# EPS_MPPT_Y_OR_MPB.net
KiCad netlist of a schematic drawn in Altium Designer
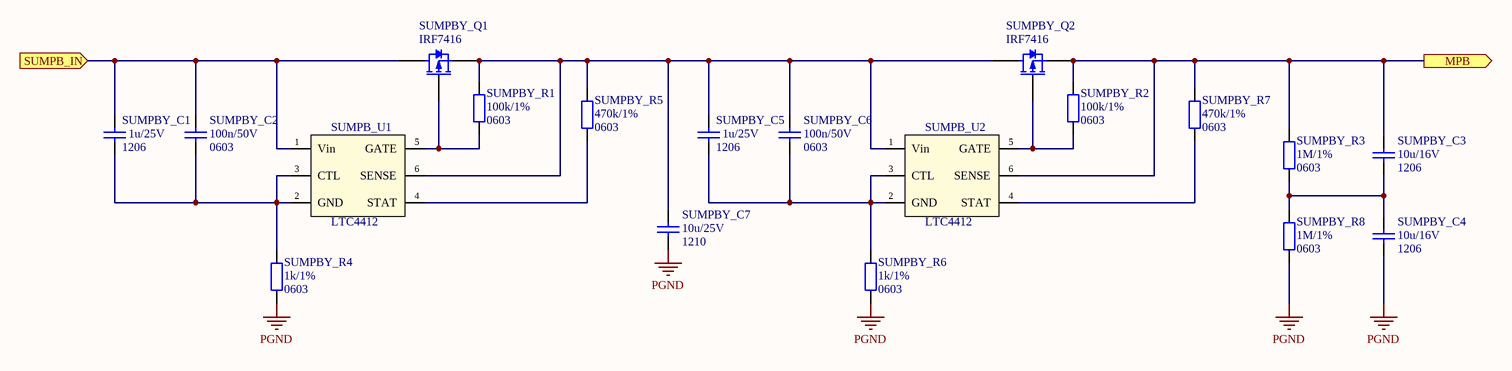
[diagram p0: EPS_MPPT_Y_OR_MPB.SchDoc]

(export (version "E")
  (design (tool "Eeschema 10.0.6"))
  (components
    (comp (ref "SUMPBY_C1")
      (value "1u/25V")
      (footprint "SMD_Capacitor_1206")
      (description "Ceramic Cap Kemet COTS 1u/25V X7R 1206")
      (fields
        (field (name "MANUFACTURERPARTNUMBER") "C1206T105K3RALTU")
        (field (name "MANUFACTURER") "Kemet")
        (field (name "PACKAGE") "1206")
      )
      (libsource (lib "capacitors") (part "Cer_C1206T105K3RALTU"))
    )
    (comp (ref "SUMPBY_C2")
      (value "100n/50V")
      (footprint "SMD_Capacitor_0603")
      (description "Ceramic Cap Murata Automotive 100n/50V X7R 0603")
      (fields
        (field (name "MANUFACTURER") "Murata")
        (field (name "MANUFACTURERPARTNUMBER") "GCJ188R71H104KA12D")
        (field (name "PACKAGE") "0603")
      )
      (libsource (lib "capacitors") (part "Cer_GCJ188R71H104KA12D"))
    )
    (comp (ref "SUMPBY_C3")
      (value "10u/16V")
      (footprint "SMD_Capacitor_1206")
      (description "Ceramic Cap Kemet COTS 10u/16V X7R 1206")
      (fields
        (field (name "MANUFACTURERPARTNUMBER") "C1206T106K4RACTU")
        (field (name "MANUFACTURER") "Kemet")
        (field (name "PACKGE") "1206")
      )
      (libsource (lib "capacitors") (part "Cer_C1206T106K4RACTU"))
    )
    (comp (ref "SUMPBY_C4")
      (value "10u/16V")
      (footprint "SMD_Capacitor_1206")
      (description "Ceramic Cap Kemet COTS 10u/16V X7R 1206")
      (fields
        (field (name "MANUFACTURERPARTNUMBER") "C1206T106K4RACTU")
        (field (name "MANUFACTURER") "Kemet")
        (field (name "PACKGE") "1206")
      )
      (libsource (lib "capacitors") (part "Cer_C1206T106K4RACTU"))
    )
    (comp (ref "SUMPBY_C5")
      (value "1u/25V")
      (footprint "SMD_Capacitor_1206")
      (description "Ceramic Cap Kemet COTS 1u/25V X7R 1206")
      (fields
        (field (name "MANUFACTURERPARTNUMBER") "C1206T105K3RALTU")
        (field (name "MANUFACTURER") "Kemet")
        (field (name "PACKAGE") "1206")
      )
      (libsource (lib "capacitors") (part "Cer_C1206T105K3RALTU"))
    )
    (comp (ref "SUMPBY_C6")
      (value "100n/50V")
      (footprint "SMD_Capacitor_0603")
      (description "Ceramic Cap Murata Automotive 100n/50V X7R 0603")
      (fields
        (field (name "MANUFACTURER") "Murata")
        (field (name "MANUFACTURERPARTNUMBER") "GCJ188R71H104KA12D")
        (field (name "PACKAGE") "0603")
      )
      (libsource (lib "capacitors") (part "Cer_GCJ188R71H104KA12D"))
    )
    (comp (ref "SUMPBY_C7")
      (value "10u/25V")
      (footprint "SMD_Capacitor_1210")
      (description "Ceramic Cap Murata Automotive 10u/25V X7R 1210")
      (fields
        (field (name "MANUFACTURER") "Murata")
        (field (name "MANUFACTURERPARTNUMBER") "GCJ32ER71E106KA12L")
        (field (name "PACKAGE") "1210")
      )
      (libsource (lib "capacitors") (part "Cer_GCJ32ER71E106KA12L"))
    )
    (comp (ref "SUMPBY_Q1")
      (value "IRF7416")
      (footprint "SOIC-8-N_SSSGDDDD")
      (description "10A/30V HEXFET Power P-MOSFET.")
      (fields (field (name "MANUFACTURER") "International Rectifier"))
      (libsource (lib "transistors") (part "IRF7416"))
    )
    (comp (ref "SUMPBY_Q2")
      (value "IRF7416")
      (footprint "SOIC-8-N_SSSGDDDD")
      (description "10A/30V HEXFET Power P-MOSFET.")
      (fields (field (name "MANUFACTURER") "International Rectifier"))
      (libsource (lib "transistors") (part "IRF7416"))
    )
    (comp (ref "SUMPBY_R1")
      (value "100k/1%")
      (footprint "SMD_Resistor_0603")
      (fields (field (name "PACKAGE") "0603"))
      (libsource (lib "resistors") (part "Res"))
    )
    (comp (ref "SUMPBY_R2")
      (value "100k/1%")
      (footprint "SMD_Resistor_0603")
      (fields (field (name "PACKAGE") "0603"))
      (libsource (lib "resistors") (part "Res"))
    )
    (comp (ref "SUMPBY_R3")
      (value "1M/1%")
      (footprint "SMD_Resistor_0603")
      (fields (field (name "PACKAGE") "0603"))
      (libsource (lib "resistors") (part "Res"))
    )
    (comp (ref "SUMPBY_R4")
      (value "1k/1%")
      (footprint "SMD_Resistor_0603")
      (fields (field (name "PACKAGE") "0603"))
      (libsource (lib "resistors") (part "Res"))
    )
    (comp (ref "SUMPBY_R5")
      (value "470k/1%")
      (footprint "SMD_Resistor_0603")
      (fields (field (name "PACKAGE") "0603"))
      (libsource (lib "resistors") (part "Res"))
    )
    (comp (ref "SUMPBY_R6")
      (value "1k/1%")
      (footprint "SMD_Resistor_0603")
      (fields (field (name "PACKAGE") "0603"))
      (libsource (lib "resistors") (part "Res"))
    )
    (comp (ref "SUMPBY_R7")
      (value "470k/1%")
      (footprint "SMD_Resistor_0603")
      (fields (field (name "PACKAGE") "0603"))
      (libsource (lib "resistors") (part "Res"))
    )
    (comp (ref "SUMPBY_R8")
      (value "1M/1%")
      (footprint "SMD_Resistor_0603")
      (fields (field (name "PACKAGE") "0603"))
      (libsource (lib "resistors") (part "Res"))
    )
    (comp (ref "SUMPB_U1")
      (value "LTC4412")
      (footprint "SOT23-6")
      (description "Ideal Diode, Low Loss PowerPath Controller.")
      (fields (field (name "MANUFACTURER") "Linear Technology"))
      (libsource (lib "microcircuits") (part "LTC4412"))
    )
    (comp (ref "SUMPB_U2")
      (value "LTC4412")
      (footprint "SOT23-6")
      (description "Ideal Diode, Low Loss PowerPath Controller.")
      (fields (field (name "MANUFACTURER") "Linear Technology"))
      (libsource (lib "microcircuits") (part "LTC4412"))
    )
  )
  (nets
    (net (code "1") (name "/MPB") (class "Default")
      (node (ref "SUMPBY_C3") (pin "1") (pinfunction "1_1") (pintype "passive"))
      (node (ref "SUMPBY_Q2") (pin "S") (pinfunction "S_S") (pintype "passive"))
      (node (ref "SUMPBY_R2") (pin "1") (pinfunction "1_1") (pintype "passive"))
      (node (ref "SUMPBY_R3") (pin "1") (pinfunction "1_1") (pintype "passive"))
      (node (ref "SUMPBY_R7") (pin "1") (pinfunction "1_1") (pintype "passive"))
      (node (ref "SUMPB_U2") (pin "6") (pinfunction "SENSE_6") (pintype "passive"))
    )
    (net (code "2") (name "/SUMPB_IN") (class "Default")
      (node (ref "SUMPBY_C1") (pin "1") (pinfunction "1_1") (pintype "passive"))
      (node (ref "SUMPBY_C2") (pin "1") (pinfunction "1_1") (pintype "passive"))
      (node (ref "SUMPBY_Q1") (pin "D") (pinfunction "D_D") (pintype "passive"))
      (node (ref "SUMPB_U1") (pin "1") (pinfunction "Vin_1") (pintype "passive"))
    )
    (net (code "3") (name "Net-(SUMPBY_C3-Pad2)") (class "Default")
      (node (ref "SUMPBY_C3") (pin "2") (pinfunction "2_2") (pintype "passive"))
      (node (ref "SUMPBY_C4") (pin "1") (pinfunction "1_1") (pintype "passive"))
      (node (ref "SUMPBY_R3") (pin "2") (pinfunction "2_2") (pintype "passive"))
      (node (ref "SUMPBY_R8") (pin "1") (pinfunction "1_1") (pintype "passive"))
    )
    (net (code "4") (name "Net-(SUMPB_U1-CTL)") (class "Default")
      (node (ref "SUMPBY_C1") (pin "2") (pinfunction "2_2") (pintype "passive"))
      (node (ref "SUMPBY_C2") (pin "2") (pinfunction "2_2") (pintype "passive"))
      (node (ref "SUMPBY_R4") (pin "1") (pinfunction "1_1") (pintype "passive"))
      (node (ref "SUMPB_U1") (pin "2") (pinfunction "GND_2") (pintype "passive"))
      (node (ref "SUMPB_U1") (pin "3") (pinfunction "CTL_3") (pintype "passive"))
    )
    (net (code "5") (name "Net-(SUMPB_U1-GATE)") (class "Default")
      (node (ref "SUMPBY_Q1") (pin "G") (pinfunction "G_G") (pintype "passive"))
      (node (ref "SUMPBY_R1") (pin "2") (pinfunction "2_2") (pintype "passive"))
      (node (ref "SUMPB_U1") (pin "5") (pinfunction "GATE_5") (pintype "passive"))
    )
    (net (code "6") (name "Net-(SUMPB_U1-SENSE)") (class "Default")
      (node (ref "SUMPBY_C5") (pin "1") (pinfunction "1_1") (pintype "passive"))
      (node (ref "SUMPBY_C6") (pin "1") (pinfunction "1_1") (pintype "passive"))
      (node (ref "SUMPBY_C7") (pin "1") (pinfunction "1_1") (pintype "passive"))
      (node (ref "SUMPBY_Q1") (pin "S") (pinfunction "S_S") (pintype "passive"))
      (node (ref "SUMPBY_Q2") (pin "D") (pinfunction "D_D") (pintype "passive"))
      (node (ref "SUMPBY_R1") (pin "1") (pinfunction "1_1") (pintype "passive"))
      (node (ref "SUMPBY_R5") (pin "1") (pinfunction "1_1") (pintype "passive"))
      (node (ref "SUMPB_U1") (pin "6") (pinfunction "SENSE_6") (pintype "passive"))
      (node (ref "SUMPB_U2") (pin "1") (pinfunction "Vin_1") (pintype "passive"))
    )
    (net (code "7") (name "Net-(SUMPB_U1-STAT)") (class "Default")
      (node (ref "SUMPBY_R5") (pin "2") (pinfunction "2_2") (pintype "passive"))
      (node (ref "SUMPB_U1") (pin "4") (pinfunction "STAT_4") (pintype "passive"))
    )
    (net (code "8") (name "Net-(SUMPB_U2-CTL)") (class "Default")
      (node (ref "SUMPBY_C5") (pin "2") (pinfunction "2_2") (pintype "passive"))
      (node (ref "SUMPBY_C6") (pin "2") (pinfunction "2_2") (pintype "passive"))
      (node (ref "SUMPBY_R6") (pin "1") (pinfunction "1_1") (pintype "passive"))
      (node (ref "SUMPB_U2") (pin "2") (pinfunction "GND_2") (pintype "passive"))
      (node (ref "SUMPB_U2") (pin "3") (pinfunction "CTL_3") (pintype "passive"))
    )
    (net (code "9") (name "Net-(SUMPB_U2-GATE)") (class "Default")
      (node (ref "SUMPBY_Q2") (pin "G") (pinfunction "G_G") (pintype "passive"))
      (node (ref "SUMPBY_R2") (pin "2") (pinfunction "2_2") (pintype "passive"))
      (node (ref "SUMPB_U2") (pin "5") (pinfunction "GATE_5") (pintype "passive"))
    )
    (net (code "10") (name "Net-(SUMPB_U2-STAT)") (class "Default")
      (node (ref "SUMPBY_R7") (pin "2") (pinfunction "2_2") (pintype "passive"))
      (node (ref "SUMPB_U2") (pin "4") (pinfunction "STAT_4") (pintype "passive"))
    )
    (net (code "11") (name "PGND") (class "Default")
      (node (ref "SUMPBY_C4") (pin "2") (pinfunction "2_2") (pintype "passive"))
      (node (ref "SUMPBY_C7") (pin "2") (pinfunction "2_2") (pintype "passive"))
      (node (ref "SUMPBY_R4") (pin "2") (pinfunction "2_2") (pintype "passive"))
      (node (ref "SUMPBY_R6") (pin "2") (pinfunction "2_2") (pintype "passive"))
      (node (ref "SUMPBY_R8") (pin "2") (pinfunction "2_2") (pintype "passive"))
    )
  )
)
